# Sheet1.net
KiCad netlist of a schematic drawn in Altium Designer
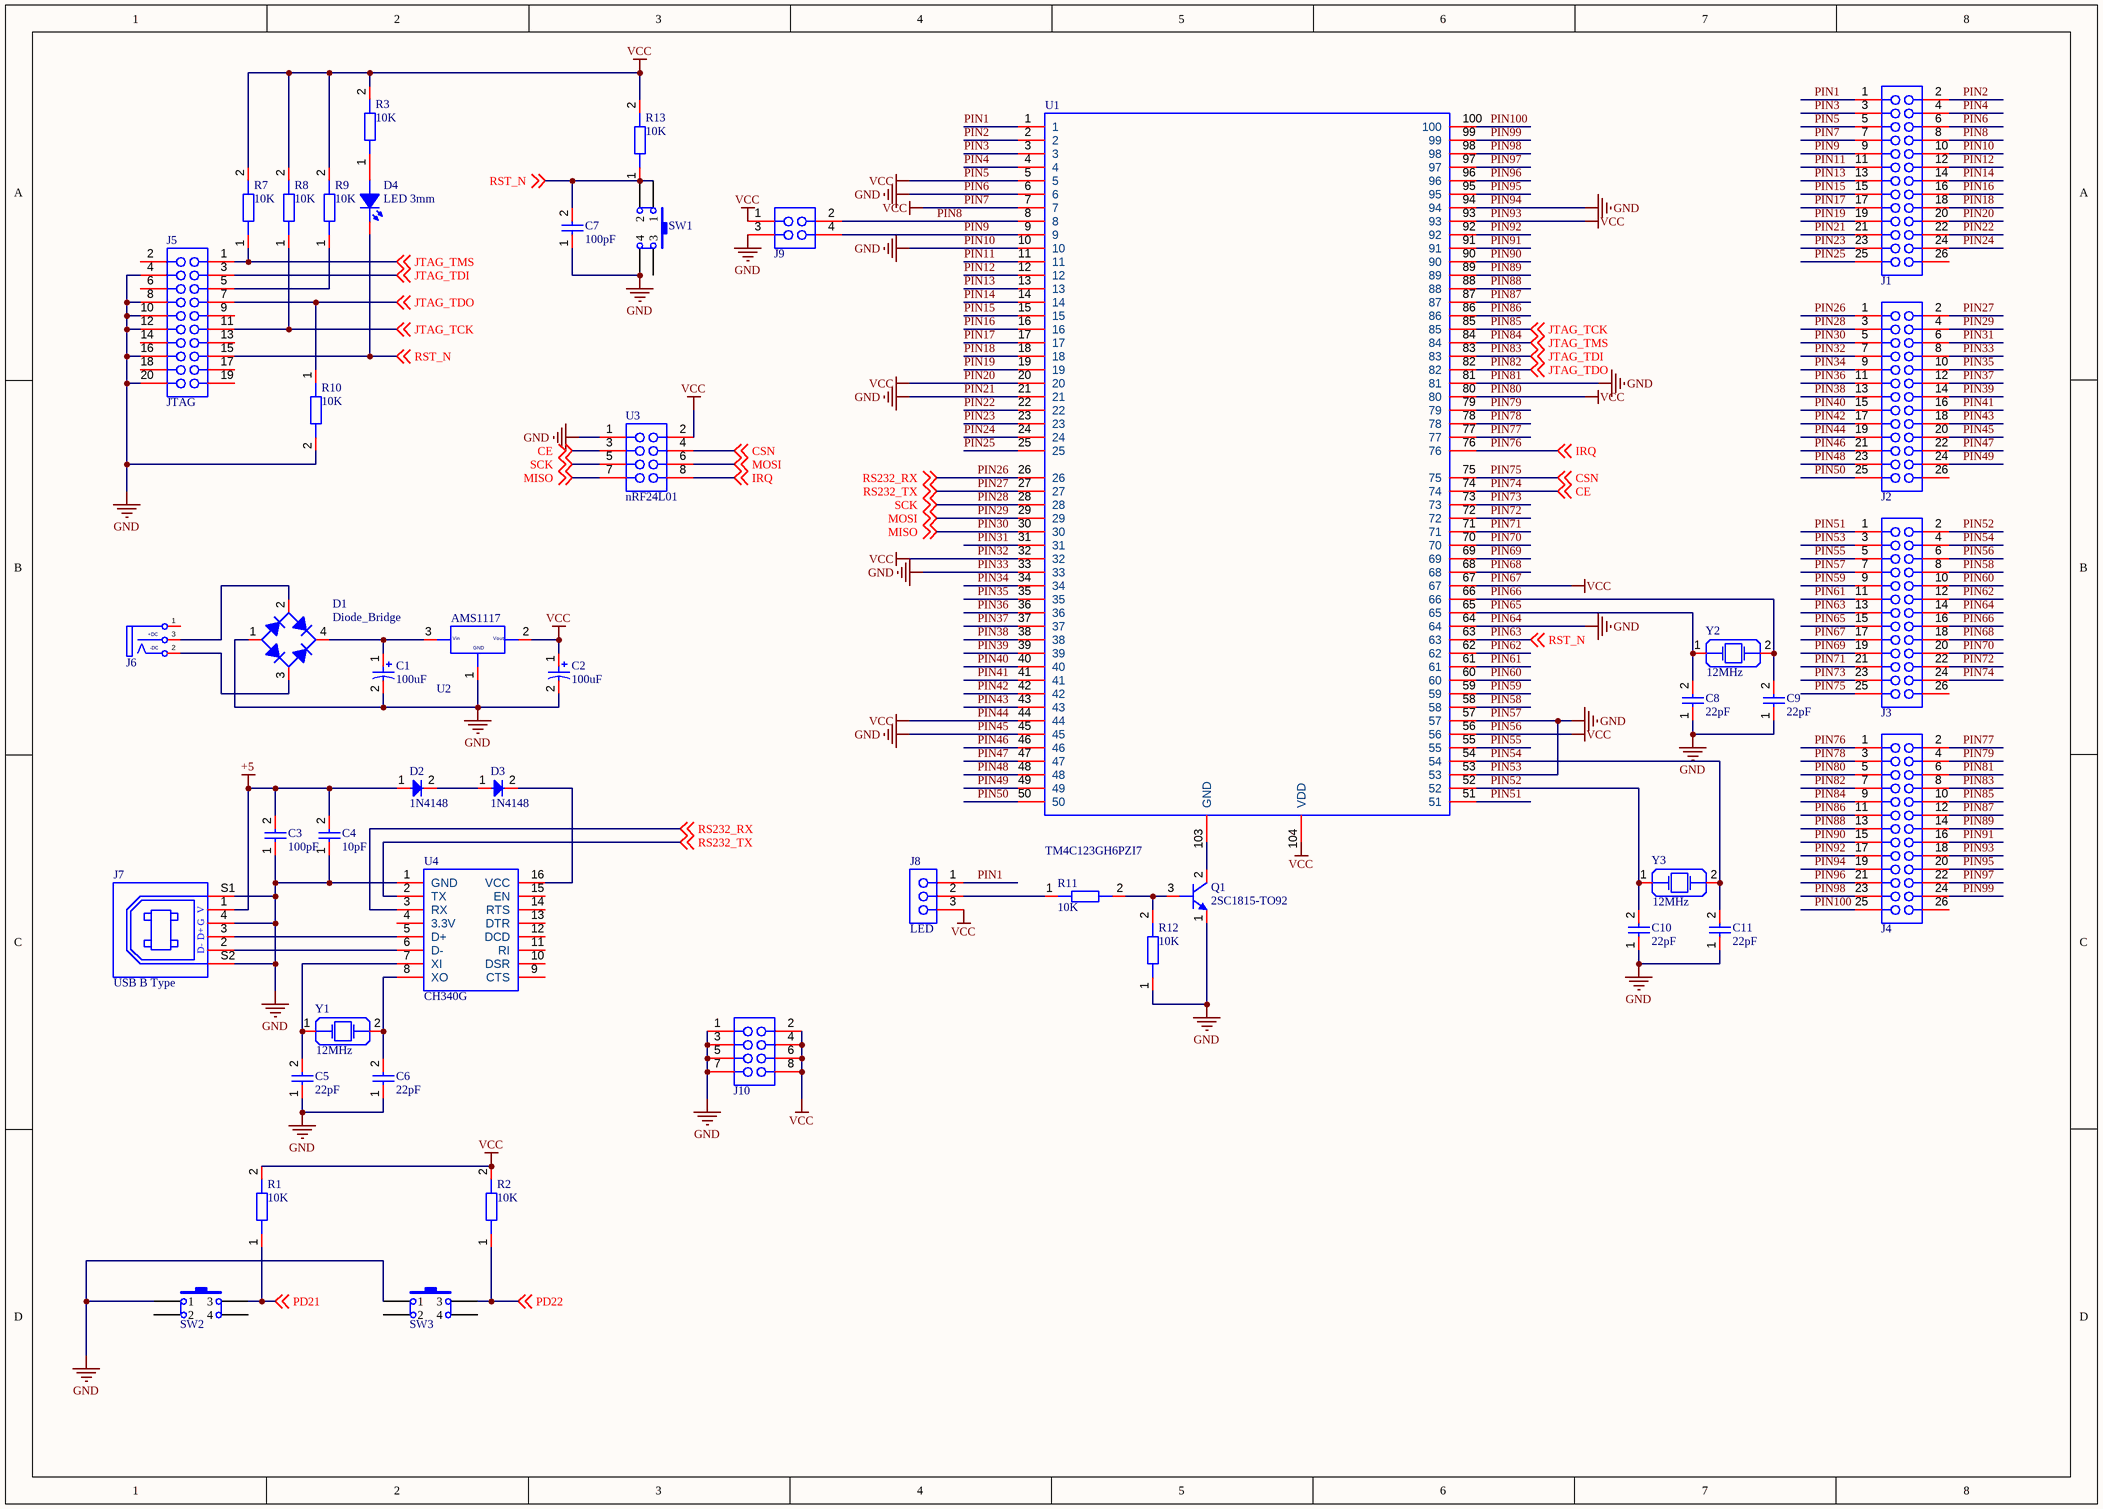
[diagram p0: Sheet1.SchDoc]

(export (version "E")
  (design (tool "Eeschema 10.0.6"))
  (components
    (comp (ref "C1")
      (value "100uF")
      (footprint "CAP_RAD_D8x11.5_POL_BK")
      (libsource (lib "SMDLibrary") (part "Capacitor(Radian)"))
    )
    (comp (ref "C2")
      (value "100uF")
      (footprint "CAP_RAD_D8x11.5_POL_BK")
      (libsource (lib "SMDLibrary") (part "Capacitor(Radian)"))
    )
    (comp (ref "C3")
      (value "100pF")
      (footprint "CAP_DISC_PITCH_2.54MM")
      (libsource (lib "SMDLibrary") (part "Capacitors(Disc)"))
    )
    (comp (ref "C4")
      (value "10pF")
      (footprint "CAP_DISC_PITCH_2.54MM")
      (libsource (lib "SMDLibrary") (part "Capacitors(Disc)"))
    )
    (comp (ref "C5")
      (value "22pF")
      (footprint "CAP_DISC_PITCH_2.54MM")
      (libsource (lib "SMDLibrary") (part "Capacitors(Disc)"))
    )
    (comp (ref "C6")
      (value "22pF")
      (footprint "CAP_DISC_PITCH_2.54MM")
      (libsource (lib "SMDLibrary") (part "Capacitors(Disc)"))
    )
    (comp (ref "C7")
      (value "100pF")
      (footprint "CAP_DISC_PITCH_2.54MM")
      (libsource (lib "SMDLibrary") (part "Capacitors(Disc)"))
    )
    (comp (ref "C8")
      (value "22pF")
      (footprint "CAP_DISC_PITCH_2.54MM")
      (libsource (lib "SMDLibrary") (part "Capacitors(Disc)"))
    )
    (comp (ref "C9")
      (value "22pF")
      (footprint "CAP_DISC_PITCH_2.54MM")
      (libsource (lib "SMDLibrary") (part "Capacitors(Disc)"))
    )
    (comp (ref "C10")
      (value "22pF")
      (footprint "CAP_DISC_PITCH_2.54MM")
      (libsource (lib "SMDLibrary") (part "Capacitors(Disc)"))
    )
    (comp (ref "C11")
      (value "22pF")
      (footprint "CAP_DISC_PITCH_2.54MM")
      (libsource (lib "SMDLibrary") (part "Capacitors(Disc)"))
    )
    (comp (ref "D1")
      (value "Diode_Bridge")
      (footprint "DIODE_2A")
      (libsource (lib "SMDLibrary") (part "Diode_Bridge"))
    )
    (comp (ref "D2")
      (value "1N4148")
      (footprint "DO-35")
      (libsource (lib "SMDLibrary") (part "Diode 1N4148"))
    )
    (comp (ref "D3")
      (value "1N4148")
      (footprint "DO-35")
      (libsource (lib "SMDLibrary") (part "Diode 1N4148"))
    )
    (comp (ref "D4") (value "LED 3mm") (footprint "LED-3MM") (libsource (lib "SMDLibrary") (part "LED 3mm")))
    (comp (ref "J1")
      (value "Header 13x2 TH Pitch 2.54mm")
      (footprint "Header 13x2 TH Pitch 2.54mm")
      (libsource (lib "SMDLibrary") (part "Header 13x2 TH Pitch 2.54mm"))
    )
    (comp (ref "J2")
      (value "Header 13x2 TH Pitch 2.54mm")
      (footprint "Header 13x2 TH Pitch 2.54mm")
      (libsource (lib "SMDLibrary") (part "Header 13x2 TH Pitch 2.54mm"))
    )
    (comp (ref "J3")
      (value "Header 13x2 TH Pitch 2.54mm")
      (footprint "Header 13x2 TH Pitch 2.54mm")
      (libsource (lib "SMDLibrary") (part "Header 13x2 TH Pitch 2.54mm"))
    )
    (comp (ref "J4")
      (value "Header 13x2 TH Pitch 2.54mm")
      (footprint "Header 13x2 TH Pitch 2.54mm")
      (libsource (lib "SMDLibrary") (part "Header 13x2 TH Pitch 2.54mm"))
    )
    (comp (ref "J5")
      (value "JTAG")
      (footprint "IDC_CONNECTOR_20_2.54")
      (libsource (lib "SMDLibrary") (part "IDC_CONNECTOR_10x2"))
    )
    (comp (ref "J6") (value "Connector") (footprint "JACK-DC") (libsource (lib "SMDLibrary") (part "JackDC")))
    (comp (ref "J7")
      (value "USB B Type")
      (footprint "USB-B-TYPE")
      (libsource (lib "SMDLibrary") (part "USB B Type"))
    )
    (comp (ref "J8")
      (value "LED")
      (footprint "Header 3x1 TH Pitch 2.54mm")
      (libsource (lib "SMDLibrary") (part "Header 3x1 TH Pitch 2.54mm"))
    )
    (comp (ref "J9")
      (value "Header 2x2 TH Pitch 2.54mm")
      (footprint "Header 2x2 TH Pitch 2.54mm")
      (libsource (lib "SMDLibrary") (part "Header 2x2 TH Pitch 2.54mm"))
    )
    (comp (ref "J10")
      (value "Header 4x2 TH Pitch 2.54mm")
      (footprint "Header 4x2 TH Pitch 2.54mm")
      (libsource (lib "SMDLibrary") (part "Header 4x2 TH Pitch 2.54mm"))
    )
    (comp (ref "Q1")
      (value "2SC1815-TO92")
      (footprint "TO-92")
      (libsource (lib "SMDLibrary") (part "2SC1815-TO92"))
    )
    (comp (ref "R1")
      (value "10K")
      (footprint "RES-0.25W-H-MF")
      (libsource (lib "SMDLibrary") (part "Resistors THD"))
    )
    (comp (ref "R2")
      (value "10K")
      (footprint "RES-0.25W-H-MF")
      (libsource (lib "SMDLibrary") (part "Resistors THD"))
    )
    (comp (ref "R3")
      (value "10K")
      (footprint "RES-0.25W-H-MF")
      (libsource (lib "SMDLibrary") (part "Resistors THD"))
    )
    (comp (ref "R7")
      (value "10K")
      (footprint "RES-0.25W-H-MF")
      (libsource (lib "SMDLibrary") (part "Resistors THD"))
    )
    (comp (ref "R8")
      (value "10K")
      (footprint "RES-0.25W-H-MF")
      (libsource (lib "SMDLibrary") (part "Resistors THD"))
    )
    (comp (ref "R9")
      (value "10K")
      (footprint "RES-0.25W-H-MF")
      (libsource (lib "SMDLibrary") (part "Resistors THD"))
    )
    (comp (ref "R10")
      (value "10K")
      (footprint "RES-0.25W-H-MF")
      (libsource (lib "") (part "Resistors THD_2"))
    )
    (comp (ref "R11")
      (value "10K")
      (footprint "RES-0.25W-H-MF")
      (libsource (lib "") (part "Resistors THD_1"))
    )
    (comp (ref "R12")
      (value "10K")
      (footprint "RES-0.25W-H-MF")
      (libsource (lib "SMDLibrary") (part "Resistors THD"))
    )
    (comp (ref "R13")
      (value "10K")
      (footprint "RES-0.25W-H-MF")
      (libsource (lib "SMDLibrary") (part "Resistors THD"))
    )
    (comp (ref "SW1")
      (value "Button1")
      (footprint "BUTTON_HOLE_5.0mm")
      (libsource (lib "SMDLibrary") (part "Button1"))
    )
    (comp (ref "SW2")
      (value "Button1")
      (footprint "BUTTON_HOLE_5.0mm")
      (libsource (lib "SMDLibrary") (part "Button1"))
    )
    (comp (ref "SW3")
      (value "Button1")
      (footprint "BUTTON_HOLE_5.0mm")
      (libsource (lib "SMDLibrary") (part "Button1"))
    )
    (comp (ref "U1")
      (value "TM4C123GH6PZI7")
      (footprint "QFP100-0.5 SOCKET PINOUT")
      (libsource (lib "SMDLibrary") (part "TM4C123GH6PZI7"))
    )
    (comp (ref "U2")
      (value "AMS1117")
      (footprint "SOT223-3")
      (libsource (lib "SMDLibrary") (part "AMS1117(SOT-223)"))
    )
    (comp (ref "U3")
      (value "nRF24L01")
      (footprint "nRF24L01")
      (libsource (lib "SMDLibrary") (part "nRF24L01"))
    )
    (comp (ref "U4")
      (value "CH340G")
      (footprint "SOP16_1.27_3.8")
      (libsource (lib "SMDLibrary") (part "CH340G"))
    )
    (comp (ref "Y1") (value "12MHz") (footprint "HC-49S") (libsource (lib "SMDLibrary") (part "Crystal")))
    (comp (ref "Y2") (value "12MHz") (footprint "HC-49S") (libsource (lib "SMDLibrary") (part "Crystal")))
    (comp (ref "Y3") (value "12MHz") (footprint "HC-49S") (libsource (lib "SMDLibrary") (part "Crystal")))
  )
  (nets
    (net (code "1") (name "+5") (class "Default")
      (node (ref "C3") (pin "2") (pinfunction "2_2") (pintype "passive"))
      (node (ref "C4") (pin "2") (pinfunction "2_2") (pintype "passive"))
      (node (ref "D2") (pin "1") (pinfunction "1_1") (pintype "passive"))
      (node (ref "J7") (pin "1") (pinfunction "1_1") (pintype "passive"))
    )
    (net (code "2") (name "/PIN1") (class "Default")
      (node (ref "J1") (pin "1") (pinfunction "1_1") (pintype "passive"))
      (node (ref "J8") (pin "1") (pinfunction "1_1") (pintype "passive"))
      (node (ref "U1") (pin "1") (pinfunction "1_1") (pintype "passive"))
    )
    (net (code "3") (name "/PIN2") (class "Default")
      (node (ref "J1") (pin "2") (pinfunction "2_2") (pintype "passive"))
      (node (ref "U1") (pin "2") (pinfunction "2_2") (pintype "passive"))
    )
    (net (code "4") (name "/PIN3") (class "Default")
      (node (ref "J1") (pin "3") (pinfunction "3_3") (pintype "passive"))
      (node (ref "U1") (pin "3") (pinfunction "3_3") (pintype "passive"))
    )
    (net (code "5") (name "/PIN4") (class "Default")
      (node (ref "J1") (pin "4") (pinfunction "4_4") (pintype "passive"))
      (node (ref "U1") (pin "4") (pinfunction "4_4") (pintype "passive"))
    )
    (net (code "6") (name "/PIN8") (class "Default")
      (node (ref "J1") (pin "8") (pinfunction "8_8") (pintype "passive"))
      (node (ref "J9") (pin "2") (pinfunction "2_2") (pintype "passive"))
      (node (ref "U1") (pin "8") (pinfunction "8_8") (pintype "passive"))
    )
    (net (code "7") (name "/PIN9") (class "Default")
      (node (ref "J1") (pin "9") (pinfunction "9_9") (pintype "passive"))
      (node (ref "J9") (pin "4") (pinfunction "4_4") (pintype "passive"))
      (node (ref "U1") (pin "9") (pinfunction "9_9") (pintype "passive"))
    )
    (net (code "8") (name "/PIN11") (class "Default")
      (node (ref "J1") (pin "11") (pinfunction "11_11") (pintype "passive"))
      (node (ref "U1") (pin "11") (pinfunction "11_11") (pintype "passive"))
    )
    (net (code "9") (name "/PIN12") (class "Default")
      (node (ref "J1") (pin "12") (pinfunction "12_12") (pintype "passive"))
      (node (ref "U1") (pin "12") (pinfunction "12_12") (pintype "passive"))
    )
    (net (code "10") (name "/PIN13") (class "Default")
      (node (ref "J1") (pin "13") (pinfunction "13_13") (pintype "passive"))
      (node (ref "U1") (pin "13") (pinfunction "13_13") (pintype "passive"))
    )
    (net (code "11") (name "/PIN14") (class "Default")
      (node (ref "J1") (pin "14") (pinfunction "14_14") (pintype "passive"))
      (node (ref "U1") (pin "14") (pinfunction "14_14") (pintype "passive"))
    )
    (net (code "12") (name "/PIN15") (class "Default")
      (node (ref "J1") (pin "15") (pinfunction "15_15") (pintype "passive"))
      (node (ref "U1") (pin "15") (pinfunction "15_15") (pintype "passive"))
    )
    (net (code "13") (name "/PIN16") (class "Default")
      (node (ref "J1") (pin "16") (pinfunction "16_16") (pintype "passive"))
      (node (ref "U1") (pin "16") (pinfunction "16_16") (pintype "passive"))
    )
    (net (code "14") (name "/PIN17") (class "Default")
      (node (ref "J1") (pin "17") (pinfunction "17_17") (pintype "passive"))
      (node (ref "U1") (pin "17") (pinfunction "17_17") (pintype "passive"))
    )
    (net (code "15") (name "/PIN18") (class "Default")
      (node (ref "J1") (pin "18") (pinfunction "18_18") (pintype "passive"))
      (node (ref "U1") (pin "18") (pinfunction "18_18") (pintype "passive"))
    )
    (net (code "16") (name "/PIN19") (class "Default")
      (node (ref "J1") (pin "19") (pinfunction "19_19") (pintype "passive"))
      (node (ref "U1") (pin "19") (pinfunction "19_19") (pintype "passive"))
    )
    (net (code "17") (name "/PIN22") (class "Default")
      (node (ref "J1") (pin "22") (pinfunction "22_22") (pintype "passive"))
      (node (ref "U1") (pin "22") (pinfunction "22_22") (pintype "passive"))
    )
    (net (code "18") (name "/PIN23") (class "Default")
      (node (ref "J1") (pin "23") (pinfunction "23_23") (pintype "passive"))
      (node (ref "U1") (pin "23") (pinfunction "23_23") (pintype "passive"))
    )
    (net (code "19") (name "/PIN24") (class "Default")
      (node (ref "J1") (pin "24") (pinfunction "24_24") (pintype "passive"))
      (node (ref "U1") (pin "24") (pinfunction "24_24") (pintype "passive"))
    )
    (net (code "20") (name "/PIN25") (class "Default")
      (node (ref "J1") (pin "25") (pinfunction "25_25") (pintype "passive"))
      (node (ref "U1") (pin "25") (pinfunction "25_25") (pintype "passive"))
    )
    (net (code "21") (name "/PIN31") (class "Default")
      (node (ref "J2") (pin "6") (pinfunction "6_6") (pintype "passive"))
      (node (ref "U1") (pin "31") (pinfunction "31_31") (pintype "passive"))
    )
    (net (code "22") (name "/PIN34") (class "Default")
      (node (ref "J2") (pin "9") (pinfunction "9_9") (pintype "passive"))
      (node (ref "U1") (pin "34") (pinfunction "34_34") (pintype "passive"))
    )
    (net (code "23") (name "/PIN35") (class "Default")
      (node (ref "J2") (pin "10") (pinfunction "10_10") (pintype "passive"))
      (node (ref "U1") (pin "35") (pinfunction "35_35") (pintype "passive"))
    )
    (net (code "24") (name "/PIN36") (class "Default")
      (node (ref "J2") (pin "11") (pinfunction "11_11") (pintype "passive"))
      (node (ref "U1") (pin "36") (pinfunction "36_36") (pintype "passive"))
    )
    (net (code "25") (name "/PIN37") (class "Default")
      (node (ref "J2") (pin "12") (pinfunction "12_12") (pintype "passive"))
      (node (ref "U1") (pin "37") (pinfunction "37_37") (pintype "passive"))
    )
    (net (code "26") (name "/PIN38") (class "Default")
      (node (ref "J2") (pin "13") (pinfunction "13_13") (pintype "passive"))
      (node (ref "U1") (pin "38") (pinfunction "38_38") (pintype "passive"))
    )
    (net (code "27") (name "/PIN39") (class "Default")
      (node (ref "J2") (pin "14") (pinfunction "14_14") (pintype "passive"))
      (node (ref "U1") (pin "39") (pinfunction "39_39") (pintype "passive"))
    )
    (net (code "28") (name "/PIN40") (class "Default")
      (node (ref "J2") (pin "15") (pinfunction "15_15") (pintype "passive"))
      (node (ref "U1") (pin "40") (pinfunction "40_40") (pintype "passive"))
    )
    (net (code "29") (name "/PIN41") (class "Default")
      (node (ref "J2") (pin "16") (pinfunction "16_16") (pintype "passive"))
      (node (ref "U1") (pin "41") (pinfunction "41_41") (pintype "passive"))
    )
    (net (code "30") (name "/PIN42") (class "Default")
      (node (ref "J2") (pin "17") (pinfunction "17_17") (pintype "passive"))
      (node (ref "U1") (pin "42") (pinfunction "42_42") (pintype "passive"))
    )
    (net (code "31") (name "/PIN43") (class "Default")
      (node (ref "J2") (pin "18") (pinfunction "18_18") (pintype "passive"))
      (node (ref "U1") (pin "43") (pinfunction "43_43") (pintype "passive"))
    )
    (net (code "32") (name "/PIN46") (class "Default")
      (node (ref "J2") (pin "21") (pinfunction "21_21") (pintype "passive"))
      (node (ref "U1") (pin "46") (pinfunction "46_46") (pintype "passive"))
    )
    (net (code "33") (name "/PIN47") (class "Default")
      (node (ref "J2") (pin "22") (pinfunction "22_22") (pintype "passive"))
      (node (ref "U1") (pin "47") (pinfunction "47_47") (pintype "passive"))
    )
    (net (code "34") (name "/PIN48") (class "Default")
      (node (ref "J2") (pin "23") (pinfunction "23_23") (pintype "passive"))
      (node (ref "U1") (pin "48") (pinfunction "48_48") (pintype "passive"))
    )
    (net (code "35") (name "/PIN49") (class "Default")
      (node (ref "J2") (pin "24") (pinfunction "24_24") (pintype "passive"))
      (node (ref "U1") (pin "49") (pinfunction "49_49") (pintype "passive"))
    )
    (net (code "36") (name "/PIN50") (class "Default")
      (node (ref "J2") (pin "25") (pinfunction "25_25") (pintype "passive"))
      (node (ref "U1") (pin "50") (pinfunction "50_50") (pintype "passive"))
    )
    (net (code "37") (name "/PIN51") (class "Default")
      (node (ref "J3") (pin "1") (pinfunction "1_1") (pintype "passive"))
      (node (ref "U1") (pin "51") (pinfunction "51_51") (pintype "passive"))
    )
    (net (code "38") (name "/PIN52") (class "Default")
      (node (ref "C10") (pin "2") (pinfunction "2_2") (pintype "passive"))
      (node (ref "J3") (pin "2") (pinfunction "2_2") (pintype "passive"))
      (node (ref "U1") (pin "52") (pinfunction "52_52") (pintype "passive"))
      (node (ref "Y3") (pin "1") (pinfunction "1_1") (pintype "passive"))
    )
    (net (code "39") (name "/PIN54") (class "Default")
      (node (ref "C11") (pin "2") (pinfunction "2_2") (pintype "passive"))
      (node (ref "J3") (pin "4") (pinfunction "4_4") (pintype "passive"))
      (node (ref "U1") (pin "54") (pinfunction "54_54") (pintype "passive"))
      (node (ref "Y3") (pin "2") (pinfunction "2_2") (pintype "passive"))
    )
    (net (code "40") (name "/PIN55") (class "Default")
      (node (ref "J3") (pin "5") (pinfunction "5_5") (pintype "passive"))
      (node (ref "U1") (pin "55") (pinfunction "55_55") (pintype "passive"))
    )
    (net (code "41") (name "/PIN58") (class "Default")
      (node (ref "J3") (pin "8") (pinfunction "8_8") (pintype "passive"))
      (node (ref "U1") (pin "58") (pinfunction "58_58") (pintype "passive"))
    )
    (net (code "42") (name "/PIN59") (class "Default")
      (node (ref "J3") (pin "9") (pinfunction "9_9") (pintype "passive"))
      (node (ref "U1") (pin "59") (pinfunction "59_59") (pintype "passive"))
    )
    (net (code "43") (name "/PIN60") (class "Default")
      (node (ref "J3") (pin "10") (pinfunction "10_10") (pintype "passive"))
      (node (ref "U1") (pin "60") (pinfunction "60_60") (pintype "passive"))
    )
    (net (code "44") (name "/PIN61") (class "Default")
      (node (ref "J3") (pin "11") (pinfunction "11_11") (pintype "passive"))
      (node (ref "U1") (pin "61") (pinfunction "61_61") (pintype "passive"))
    )
    (net (code "45") (name "/PIN62") (class "Default")
      (node (ref "J3") (pin "12") (pinfunction "12_12") (pintype "passive"))
      (node (ref "U1") (pin "62") (pinfunction "62_62") (pintype "passive"))
    )
    (net (code "46") (name "/PIN65") (class "Default")
      (node (ref "C8") (pin "2") (pinfunction "2_2") (pintype "passive"))
      (node (ref "J3") (pin "15") (pinfunction "15_15") (pintype "passive"))
      (node (ref "U1") (pin "65") (pinfunction "65_65") (pintype "passive"))
      (node (ref "Y2") (pin "1") (pinfunction "1_1") (pintype "passive"))
    )
    (net (code "47") (name "/PIN66") (class "Default")
      (node (ref "C9") (pin "2") (pinfunction "2_2") (pintype "passive"))
      (node (ref "J3") (pin "16") (pinfunction "16_16") (pintype "passive"))
      (node (ref "U1") (pin "66") (pinfunction "66_66") (pintype "passive"))
      (node (ref "Y2") (pin "2") (pinfunction "2_2") (pintype "passive"))
    )
    (net (code "48") (name "/PIN68") (class "Default")
      (node (ref "J3") (pin "18") (pinfunction "18_18") (pintype "passive"))
      (node (ref "U1") (pin "68") (pinfunction "68_68") (pintype "passive"))
    )
    (net (code "49") (name "/PIN69") (class "Default")
      (node (ref "J3") (pin "19") (pinfunction "19_19") (pintype "passive"))
      (node (ref "U1") (pin "69") (pinfunction "69_69") (pintype "passive"))
    )
    (net (code "50") (name "/PIN70") (class "Default")
      (node (ref "J3") (pin "20") (pinfunction "20_20") (pintype "passive"))
      (node (ref "U1") (pin "70") (pinfunction "70_70") (pintype "passive"))
    )
    (net (code "51") (name "/PIN71") (class "Default")
      (node (ref "J3") (pin "21") (pinfunction "21_21") (pintype "passive"))
      (node (ref "U1") (pin "71") (pinfunction "71_71") (pintype "passive"))
    )
    (net (code "52") (name "/PIN72") (class "Default")
      (node (ref "J3") (pin "22") (pinfunction "22_22") (pintype "passive"))
      (node (ref "U1") (pin "72") (pinfunction "72_72") (pintype "passive"))
    )
    (net (code "53") (name "/PIN73") (class "Default")
      (node (ref "J3") (pin "23") (pinfunction "23_23") (pintype "passive"))
      (node (ref "U1") (pin "73") (pinfunction "73_73") (pintype "passive"))
    )
    (net (code "54") (name "/PIN77") (class "Default")
      (node (ref "J4") (pin "2") (pinfunction "2_2") (pintype "passive"))
      (node (ref "U1") (pin "77") (pinfunction "77_77") (pintype "passive"))
    )
    (net (code "55") (name "/PIN78") (class "Default")
      (node (ref "J4") (pin "3") (pinfunction "3_3") (pintype "passive"))
      (node (ref "U1") (pin "78") (pinfunction "78_78") (pintype "passive"))
    )
    (net (code "56") (name "/PIN79") (class "Default")
      (node (ref "J4") (pin "4") (pinfunction "4_4") (pintype "passive"))
      (node (ref "U1") (pin "79") (pinfunction "79_79") (pintype "passive"))
    )
    (net (code "57") (name "/PIN86") (class "Default")
      (node (ref "J4") (pin "11") (pinfunction "11_11") (pintype "passive"))
      (node (ref "U1") (pin "86") (pinfunction "86_86") (pintype "passive"))
    )
    (net (code "58") (name "/PIN87") (class "Default")
      (node (ref "J4") (pin "12") (pinfunction "12_12") (pintype "passive"))
      (node (ref "U1") (pin "87") (pinfunction "87_87") (pintype "passive"))
    )
    (net (code "59") (name "/PIN88") (class "Default")
      (node (ref "J4") (pin "13") (pinfunction "13_13") (pintype "passive"))
      (node (ref "U1") (pin "88") (pinfunction "88_88") (pintype "passive"))
    )
    (net (code "60") (name "/PIN89") (class "Default")
      (node (ref "J4") (pin "14") (pinfunction "14_14") (pintype "passive"))
      (node (ref "U1") (pin "89") (pinfunction "89_89") (pintype "passive"))
    )
    (net (code "61") (name "/PIN90") (class "Default")
      (node (ref "J4") (pin "15") (pinfunction "15_15") (pintype "passive"))
      (node (ref "U1") (pin "90") (pinfunction "90_90") (pintype "passive"))
    )
    (net (code "62") (name "/PIN91") (class "Default")
      (node (ref "J4") (pin "16") (pinfunction "16_16") (pintype "passive"))
      (node (ref "U1") (pin "91") (pinfunction "91_91") (pintype "passive"))
    )
    (net (code "63") (name "/PIN92") (class "Default")
      (node (ref "J4") (pin "17") (pinfunction "17_17") (pintype "passive"))
      (node (ref "U1") (pin "92") (pinfunction "92_92") (pintype "passive"))
    )
    (net (code "64") (name "/PIN95") (class "Default")
      (node (ref "J4") (pin "20") (pinfunction "20_20") (pintype "passive"))
      (node (ref "U1") (pin "95") (pinfunction "95_95") (pintype "passive"))
    )
    (net (code "65") (name "/PIN96") (class "Default")
      (node (ref "J4") (pin "21") (pinfunction "21_21") (pintype "passive"))
      (node (ref "U1") (pin "96") (pinfunction "96_96") (pintype "passive"))
    )
    (net (code "66") (name "/PIN97") (class "Default")
      (node (ref "J4") (pin "22") (pinfunction "22_22") (pintype "passive"))
      (node (ref "U1") (pin "97") (pinfunction "97_97") (pintype "passive"))
    )
    (net (code "67") (name "/PIN98") (class "Default")
      (node (ref "J4") (pin "23") (pinfunction "23_23") (pintype "passive"))
      (node (ref "U1") (pin "98") (pinfunction "98_98") (pintype "passive"))
    )
    (net (code "68") (name "/PIN99") (class "Default")
      (node (ref "J4") (pin "24") (pinfunction "24_24") (pintype "passive"))
      (node (ref "U1") (pin "99") (pinfunction "99_99") (pintype "passive"))
    )
    (net (code "69") (name "/PIN100") (class "Default")
      (node (ref "J4") (pin "25") (pinfunction "25_25") (pintype "passive"))
      (node (ref "U1") (pin "100") (pinfunction "100_100") (pintype "passive"))
    )
    (net (code "70") (name "CE") (class "Default")
      (node (ref "J3") (pin "24") (pinfunction "24_24") (pintype "passive"))
      (node (ref "U1") (pin "74") (pinfunction "74_74") (pintype "passive"))
      (node (ref "U3") (pin "3") (pinfunction "3_3") (pintype "passive"))
    )
    (net (code "71") (name "CSN") (class "Default")
      (node (ref "J3") (pin "25") (pinfunction "25_25") (pintype "passive"))
      (node (ref "U1") (pin "75") (pinfunction "75_75") (pintype "passive"))
      (node (ref "U3") (pin "4") (pinfunction "4_4") (pintype "passive"))
    )
    (net (code "72") (name "GND") (class "Default")
      (node (ref "C1") (pin "2") (pinfunction "2_2") (pintype "passive"))
      (node (ref "C10") (pin "1") (pinfunction "1_1") (pintype "passive"))
      (node (ref "C11") (pin "1") (pinfunction "1_1") (pintype "passive"))
      (node (ref "C2") (pin "2") (pinfunction "2_2") (pintype "passive"))
      (node (ref "C3") (pin "1") (pinfunction "1_1") (pintype "passive"))
      (node (ref "C4") (pin "1") (pinfunction "1_1") (pintype "passive"))
      (node (ref "C5") (pin "1") (pinfunction "1_1") (pintype "passive"))
      (node (ref "C6") (pin "1") (pinfunction "1_1") (pintype "passive"))
      (node (ref "C7") (pin "1") (pinfunction "1_1") (pintype "passive"))
      (node (ref "C8") (pin "1") (pinfunction "1_1") (pintype "passive"))
      (node (ref "C9") (pin "1") (pinfunction "1_1") (pintype "passive"))
      (node (ref "D1") (pin "1") (pinfunction "1_1") (pintype "passive"))
      (node (ref "J1") (pin "10") (pinfunction "10_10") (pintype "passive"))
      (node (ref "J1") (pin "21") (pinfunction "21_21") (pintype "passive"))
      (node (ref "J1") (pin "6") (pinfunction "6_6") (pintype "passive"))
      (node (ref "J10") (pin "1") (pinfunction "1_1") (pintype "passive"))
      (node (ref "J10") (pin "3") (pinfunction "3_3") (pintype "passive"))
      (node (ref "J10") (pin "5") (pinfunction "5_5") (pintype "passive"))
      (node (ref "J10") (pin "7") (pinfunction "7_7") (pintype "passive"))
      (node (ref "J2") (pin "20") (pinfunction "20_20") (pintype "passive"))
      (node (ref "J2") (pin "8") (pinfunction "8_8") (pintype "passive"))
      (node (ref "J3") (pin "14") (pinfunction "14_14") (pintype "passive"))
      (node (ref "J3") (pin "3") (pinfunction "3_3") (pintype "passive"))
      (node (ref "J3") (pin "7") (pinfunction "7_7") (pintype "passive"))
      (node (ref "J4") (pin "19") (pinfunction "19_19") (pintype "passive"))
      (node (ref "J4") (pin "6") (pinfunction "6_6") (pintype "passive"))
      (node (ref "J5") (pin "10") (pinfunction "10_10") (pintype "passive"))
      (node (ref "J5") (pin "12") (pinfunction "12_12") (pintype "passive"))
      (node (ref "J5") (pin "16") (pinfunction "16_16") (pintype "passive"))
      (node (ref "J5") (pin "20") (pinfunction "20_20") (pintype "passive"))
      (node (ref "J5") (pin "4") (pinfunction "4_4") (pintype "passive"))
      (node (ref "J5") (pin "8") (pinfunction "8_8") (pintype "passive"))
      (node (ref "J7") (pin "4") (pinfunction "4_4") (pintype "passive"))
      (node (ref "J7") (pin "S1") (pinfunction "S1_S1") (pintype "passive"))
      (node (ref "J7") (pin "S2") (pinfunction "S2_S2") (pintype "passive"))
      (node (ref "J9") (pin "3") (pinfunction "3_3") (pintype "passive"))
      (node (ref "Q1") (pin "1") (pinfunction "E_1") (pintype "passive"))
      (node (ref "R10") (pin "2") (pinfunction "2_2") (pintype "passive"))
      (node (ref "R12") (pin "1") (pinfunction "1_1") (pintype "passive"))
      (node (ref "SW1") (pin "4") (pinfunction "4_4") (pintype "passive"))
      (node (ref "SW2") (pin "1") (pinfunction "1_1") (pintype "passive"))
      (node (ref "SW3") (pin "1") (pinfunction "1_1") (pintype "passive"))
      (node (ref "U1") (pin "10") (pinfunction "10_10") (pintype "passive"))
      (node (ref "U1") (pin "21") (pinfunction "21_21") (pintype "passive"))
      (node (ref "U1") (pin "33") (pinfunction "33_33") (pintype "passive"))
      (node (ref "U1") (pin "45") (pinfunction "45_45") (pintype "passive"))
      (node (ref "U1") (pin "53") (pinfunction "53_53") (pintype "passive"))
      (node (ref "U1") (pin "57") (pinfunction "57_57") (pintype "passive"))
      (node (ref "U1") (pin "6") (pinfunction "6_6") (pintype "passive"))
      (node (ref "U1") (pin "64") (pinfunction "64_64") (pintype "passive"))
      (node (ref "U1") (pin "81") (pinfunction "81_81") (pintype "passive"))
      (node (ref "U1") (pin "94") (pinfunction "94_94") (pintype "passive"))
      (node (ref "U2") (pin "1") (pinfunction "1_1") (pintype "passive"))
      (node (ref "U3") (pin "1") (pinfunction "1_1") (pintype "passive"))
      (node (ref "U4") (pin "1") (pinfunction "GND_1") (pintype "passive"))
    )
    (net (code "73") (name "IRQ") (class "Default")
      (node (ref "J4") (pin "1") (pinfunction "1_1") (pintype "passive"))
      (node (ref "U1") (pin "76") (pinfunction "76_76") (pintype "passive"))
      (node (ref "U3") (pin "8") (pinfunction "8_8") (pintype "passive"))
    )
    (net (code "74") (name "JTAG_TCK") (class "Default")
      (node (ref "J4") (pin "10") (pinfunction "10_10") (pintype "passive"))
      (node (ref "J5") (pin "11") (pinfunction "11_11") (pintype "passive"))
      (node (ref "R8") (pin "1") (pinfunction "1_1") (pintype "passive"))
      (node (ref "U1") (pin "85") (pinfunction "85_85") (pintype "passive"))
    )
    (net (code "75") (name "JTAG_TDI") (class "Default")
      (node (ref "J4") (pin "8") (pinfunction "8_8") (pintype "passive"))
      (node (ref "J5") (pin "3") (pinfunction "3_3") (pintype "passive"))
      (node (ref "U1") (pin "83") (pinfunction "83_83") (pintype "passive"))
    )
    (net (code "76") (name "JTAG_TDO") (class "Default")
      (node (ref "J4") (pin "7") (pinfunction "7_7") (pintype "passive"))
      (node (ref "J5") (pin "7") (pinfunction "7_7") (pintype "passive"))
      (node (ref "R10") (pin "1") (pinfunction "1_1") (pintype "passive"))
      (node (ref "U1") (pin "82") (pinfunction "82_82") (pintype "passive"))
    )
    (net (code "77") (name "JTAG_TMS") (class "Default")
      (node (ref "J4") (pin "9") (pinfunction "9_9") (pintype "passive"))
      (node (ref "J5") (pin "1") (pinfunction "1_1") (pintype "passive"))
      (node (ref "R7") (pin "1") (pinfunction "1_1") (pintype "passive"))
      (node (ref "U1") (pin "84") (pinfunction "84_84") (pintype "passive"))
    )
    (net (code "78") (name "MISO") (class "Default")
      (node (ref "J2") (pin "5") (pinfunction "5_5") (pintype "passive"))
      (node (ref "U1") (pin "30") (pinfunction "30_30") (pintype "passive"))
      (node (ref "U3") (pin "7") (pinfunction "7_7") (pintype "passive"))
    )
    (net (code "79") (name "MOSI") (class "Default")
      (node (ref "J2") (pin "4") (pinfunction "4_4") (pintype "passive"))
      (node (ref "U1") (pin "29") (pinfunction "29_29") (pintype "passive"))
      (node (ref "U3") (pin "6") (pinfunction "6_6") (pintype "passive"))
    )
    (net (code "80") (name "Net-(C1-Pad1)") (class "Default")
      (node (ref "C1") (pin "1") (pinfunction "1_1") (pintype "passive"))
      (node (ref "D1") (pin "4") (pinfunction "4_4") (pintype "passive"))
      (node (ref "U2") (pin "3") (pinfunction "3_3") (pintype "passive"))
    )
    (net (code "81") (name "Net-(D2-Pad2)") (class "Default")
      (node (ref "D2") (pin "2") (pinfunction "2_2") (pintype "passive"))
      (node (ref "D3") (pin "1") (pinfunction "1_1") (pintype "passive"))
    )
    (net (code "82") (name "Net-(D4-A)") (class "Default")
      (node (ref "D4") (pin "1") (pinfunction "A_1") (pintype "passive"))
      (node (ref "R3") (pin "1") (pinfunction "1_1") (pintype "passive"))
    )
    (net (code "83") (name "Net-(J5-Pad5)") (class "Default")
      (node (ref "J5") (pin "5") (pinfunction "5_5") (pintype "passive"))
      (node (ref "R9") (pin "1") (pinfunction "1_1") (pintype "passive"))
    )
    (net (code "84") (name "Net-(J6-S)") (class "Default")
      (node (ref "D1") (pin "2") (pinfunction "2_2") (pintype "passive"))
      (node (ref "J6") (pin "3") (pinfunction "S_3") (pintype "power_in"))
    )
    (net (code "85") (name "Net-(J6-TN)") (class "Default")
      (node (ref "D1") (pin "3") (pinfunction "3_3") (pintype "passive"))
      (node (ref "J6") (pin "2") (pinfunction "TN_2") (pintype "passive"))
    )
    (net (code "86") (name "Net-(J8-Pad2)") (class "Default")
      (node (ref "J8") (pin "2") (pinfunction "2_2") (pintype "passive"))
      (node (ref "R11") (pin "1") (pinfunction "1_1") (pintype "passive"))
    )
    (net (code "87") (name "Net-(Q1-B)") (class "Default")
      (node (ref "Q1") (pin "3") (pinfunction "B_3") (pintype "passive"))
      (node (ref "R11") (pin "2") (pinfunction "2_2") (pintype "passive"))
      (node (ref "R12") (pin "2") (pinfunction "2_2") (pintype "passive"))
    )
    (net (code "88") (name "Net-(Q1-C)") (class "Default")
      (node (ref "Q1") (pin "2") (pinfunction "C_2") (pintype "passive"))
      (node (ref "U1") (pin "103") (pinfunction "GND_103") (pintype "passive"))
    )
    (net (code "89") (name "Net-(U4-D+)") (class "Default")
      (node (ref "J7") (pin "3") (pinfunction "3_3") (pintype "passive"))
      (node (ref "U4") (pin "5") (pinfunction "D+_5") (pintype "passive"))
    )
    (net (code "90") (name "Net-(U4-D-)") (class "Default")
      (node (ref "J7") (pin "2") (pinfunction "2_2") (pintype "passive"))
      (node (ref "U4") (pin "6") (pinfunction "D-_6") (pintype "passive"))
    )
    (net (code "91") (name "Net-(U4-VCC)") (class "Default")
      (node (ref "D3") (pin "2") (pinfunction "2_2") (pintype "passive"))
      (node (ref "U4") (pin "16") (pinfunction "VCC_16") (pintype "passive"))
    )
    (net (code "92") (name "Net-(U4-XI)") (class "Default")
      (node (ref "C5") (pin "2") (pinfunction "2_2") (pintype "passive"))
      (node (ref "U4") (pin "7") (pinfunction "XI_7") (pintype "passive"))
      (node (ref "Y1") (pin "1") (pinfunction "1_1") (pintype "passive"))
    )
    (net (code "93") (name "Net-(U4-XO)") (class "Default")
      (node (ref "C6") (pin "2") (pinfunction "2_2") (pintype "passive"))
      (node (ref "U4") (pin "8") (pinfunction "XO_8") (pintype "passive"))
      (node (ref "Y1") (pin "2") (pinfunction "2_2") (pintype "passive"))
    )
    (net (code "94") (name "PD21") (class "Default")
      (node (ref "R1") (pin "1") (pinfunction "1_1") (pintype "passive"))
      (node (ref "SW2") (pin "3") (pinfunction "3_3") (pintype "passive"))
    )
    (net (code "95") (name "PD22") (class "Default")
      (node (ref "R2") (pin "1") (pinfunction "1_1") (pintype "passive"))
      (node (ref "SW3") (pin "3") (pinfunction "3_3") (pintype "passive"))
    )
    (net (code "96") (name "RS232_RX") (class "Default")
      (node (ref "J2") (pin "1") (pinfunction "1_1") (pintype "passive"))
      (node (ref "U1") (pin "26") (pinfunction "26_26") (pintype "passive"))
      (node (ref "U4") (pin "3") (pinfunction "RX_3") (pintype "passive"))
    )
    (net (code "97") (name "RS232_TX") (class "Default")
      (node (ref "J2") (pin "2") (pinfunction "2_2") (pintype "passive"))
      (node (ref "U1") (pin "27") (pinfunction "27_27") (pintype "passive"))
      (node (ref "U4") (pin "2") (pinfunction "TX_2") (pintype "passive"))
    )
    (net (code "98") (name "RST_N") (class "Default")
      (node (ref "C7") (pin "2") (pinfunction "2_2") (pintype "passive"))
      (node (ref "D4") (pin "2") (pinfunction "K_2") (pintype "passive"))
      (node (ref "J3") (pin "13") (pinfunction "13_13") (pintype "passive"))
      (node (ref "J5") (pin "15") (pinfunction "15_15") (pintype "passive"))
      (node (ref "R13") (pin "1") (pinfunction "1_1") (pintype "passive"))
      (node (ref "SW1") (pin "1") (pinfunction "1_1") (pintype "passive"))
      (node (ref "SW1") (pin "2") (pinfunction "2_2") (pintype "passive"))
      (node (ref "U1") (pin "63") (pinfunction "63_63") (pintype "passive"))
    )
    (net (code "99") (name "SCK") (class "Default")
      (node (ref "J2") (pin "3") (pinfunction "3_3") (pintype "passive"))
      (node (ref "U1") (pin "28") (pinfunction "28_28") (pintype "passive"))
      (node (ref "U3") (pin "5") (pinfunction "5_5") (pintype "passive"))
    )
    (net (code "100") (name "VCC") (class "Default")
      (node (ref "C2") (pin "1") (pinfunction "1_1") (pintype "passive"))
      (node (ref "J1") (pin "20") (pinfunction "20_20") (pintype "passive"))
      (node (ref "J1") (pin "5") (pinfunction "5_5") (pintype "passive"))
      (node (ref "J1") (pin "7") (pinfunction "7_7") (pintype "passive"))
      (node (ref "J10") (pin "2") (pinfunction "2_2") (pintype "passive"))
      (node (ref "J10") (pin "4") (pinfunction "4_4") (pintype "passive"))
      (node (ref "J10") (pin "6") (pinfunction "6_6") (pintype "passive"))
      (node (ref "J10") (pin "8") (pinfunction "8_8") (pintype "passive"))
      (node (ref "J2") (pin "19") (pinfunction "19_19") (pintype "passive"))
      (node (ref "J2") (pin "7") (pinfunction "7_7") (pintype "passive"))
      (node (ref "J3") (pin "17") (pinfunction "17_17") (pintype "passive"))
      (node (ref "J3") (pin "6") (pinfunction "6_6") (pintype "passive"))
      (node (ref "J4") (pin "18") (pinfunction "18_18") (pintype "passive"))
      (node (ref "J4") (pin "5") (pinfunction "5_5") (pintype "passive"))
      (node (ref "J8") (pin "3") (pinfunction "3_3") (pintype "passive"))
      (node (ref "J9") (pin "1") (pinfunction "1_1") (pintype "passive"))
      (node (ref "R1") (pin "2") (pinfunction "2_2") (pintype "passive"))
      (node (ref "R13") (pin "2") (pinfunction "2_2") (pintype "passive"))
      (node (ref "R2") (pin "2") (pinfunction "2_2") (pintype "passive"))
      (node (ref "R3") (pin "2") (pinfunction "2_2") (pintype "passive"))
      (node (ref "R7") (pin "2") (pinfunction "2_2") (pintype "passive"))
      (node (ref "R8") (pin "2") (pinfunction "2_2") (pintype "passive"))
      (node (ref "R9") (pin "2") (pinfunction "2_2") (pintype "passive"))
      (node (ref "U1") (pin "104") (pinfunction "VDD_104") (pintype "passive"))
      (node (ref "U1") (pin "20") (pinfunction "20_20") (pintype "passive"))
      (node (ref "U1") (pin "32") (pinfunction "32_32") (pintype "passive"))
      (node (ref "U1") (pin "44") (pinfunction "44_44") (pintype "passive"))
      (node (ref "U1") (pin "5") (pinfunction "5_5") (pintype "passive"))
      (node (ref "U1") (pin "56") (pinfunction "56_56") (pintype "passive"))
      (node (ref "U1") (pin "67") (pinfunction "67_67") (pintype "passive"))
      (node (ref "U1") (pin "7") (pinfunction "7_7") (pintype "passive"))
      (node (ref "U1") (pin "80") (pinfunction "80_80") (pintype "passive"))
      (node (ref "U1") (pin "93") (pinfunction "93_93") (pintype "passive"))
      (node (ref "U2") (pin "2") (pinfunction "2_2") (pintype "passive"))
      (node (ref "U3") (pin "2") (pinfunction "2_2") (pintype "passive"))
    )
    (net (code "101") (name "unconnected-(J1-Pad26)") (class "Default")
      (node (ref "J1") (pin "26") (pinfunction "26_26") (pintype "passive"))
    )
    (net (code "102") (name "unconnected-(J2-Pad26)") (class "Default")
      (node (ref "J2") (pin "26") (pinfunction "26_26") (pintype "passive"))
    )
    (net (code "103") (name "unconnected-(J3-Pad26)") (class "Default")
      (node (ref "J3") (pin "26") (pinfunction "26_26") (pintype "passive"))
    )
    (net (code "104") (name "unconnected-(J4-Pad26)") (class "Default")
      (node (ref "J4") (pin "26") (pinfunction "26_26") (pintype "passive"))
    )
    (net (code "105") (name "unconnected-(J5-Pad2)") (class "Default")
      (node (ref "J5") (pin "2") (pinfunction "2_2") (pintype "passive"))
    )
    (net (code "106") (name "unconnected-(J5-Pad6)") (class "Default")
      (node (ref "J5") (pin "6") (pinfunction "6_6") (pintype "passive"))
    )
    (net (code "107") (name "unconnected-(J5-Pad9)") (class "Default")
      (node (ref "J5") (pin "9") (pinfunction "9_9") (pintype "passive"))
    )
    (net (code "108") (name "unconnected-(J5-Pad13)") (class "Default")
      (node (ref "J5") (pin "13") (pinfunction "13_13") (pintype "passive"))
    )
    (net (code "109") (name "unconnected-(J5-Pad14)") (class "Default")
      (node (ref "J5") (pin "14") (pinfunction "14_14") (pintype "passive"))
    )
    (net (code "110") (name "unconnected-(J5-Pad17)") (class "Default")
      (node (ref "J5") (pin "17") (pinfunction "17_17") (pintype "passive"))
    )
    (net (code "111") (name "unconnected-(J5-Pad18)") (class "Default")
      (node (ref "J5") (pin "18") (pinfunction "18_18") (pintype "passive"))
    )
    (net (code "112") (name "unconnected-(J5-Pad19)") (class "Default")
      (node (ref "J5") (pin "19") (pinfunction "19_19") (pintype "passive"))
    )
    (net (code "113") (name "unconnected-(J6-T-Pad1)") (class "Default")
      (node (ref "J6") (pin "1") (pinfunction "T_1") (pintype "passive"))
    )
    (net (code "114") (name "unconnected-(SW1-Pad3)") (class "Default")
      (node (ref "SW1") (pin "3") (pinfunction "3_3") (pintype "passive"))
    )
    (net (code "115") (name "unconnected-(SW2-Pad2)") (class "Default")
      (node (ref "SW2") (pin "2") (pinfunction "2_2") (pintype "passive"))
    )
    (net (code "116") (name "unconnected-(SW2-Pad4)") (class "Default")
      (node (ref "SW2") (pin "4") (pinfunction "4_4") (pintype "passive"))
    )
    (net (code "117") (name "unconnected-(SW3-Pad2)") (class "Default")
      (node (ref "SW3") (pin "2") (pinfunction "2_2") (pintype "passive"))
    )
    (net (code "118") (name "unconnected-(SW3-Pad4)") (class "Default")
      (node (ref "SW3") (pin "4") (pinfunction "4_4") (pintype "passive"))
    )
    (net (code "119") (name "unconnected-(U4-3.3V-Pad4)") (class "Default")
      (node (ref "U4") (pin "4") (pinfunction "3.3V_4") (pintype "passive"))
    )
    (net (code "120") (name "unconnected-(U4-CTS-Pad9)") (class "Default")
      (node (ref "U4") (pin "9") (pinfunction "CTS_9") (pintype "passive"))
    )
    (net (code "121") (name "unconnected-(U4-DCD-Pad12)") (class "Default")
      (node (ref "U4") (pin "12") (pinfunction "DCD_12") (pintype "passive"))
    )
    (net (code "122") (name "unconnected-(U4-DSR-Pad10)") (class "Default")
      (node (ref "U4") (pin "10") (pinfunction "DSR_10") (pintype "passive"))
    )
    (net (code "123") (name "unconnected-(U4-DTR-Pad13)") (class "Default")
      (node (ref "U4") (pin "13") (pinfunction "DTR_13") (pintype "passive"))
    )
    (net (code "124") (name "unconnected-(U4-EN-Pad15)") (class "Default")
      (node (ref "U4") (pin "15") (pinfunction "EN_15") (pintype "passive"))
    )
    (net (code "125") (name "unconnected-(U4-RI-Pad11)") (class "Default")
      (node (ref "U4") (pin "11") (pinfunction "RI_11") (pintype "passive"))
    )
    (net (code "126") (name "unconnected-(U4-RTS-Pad14)") (class "Default")
      (node (ref "U4") (pin "14") (pinfunction "RTS_14") (pintype "passive"))
    )
  )
)
